# power.net
KiCad netlist of a schematic drawn in EAGLE
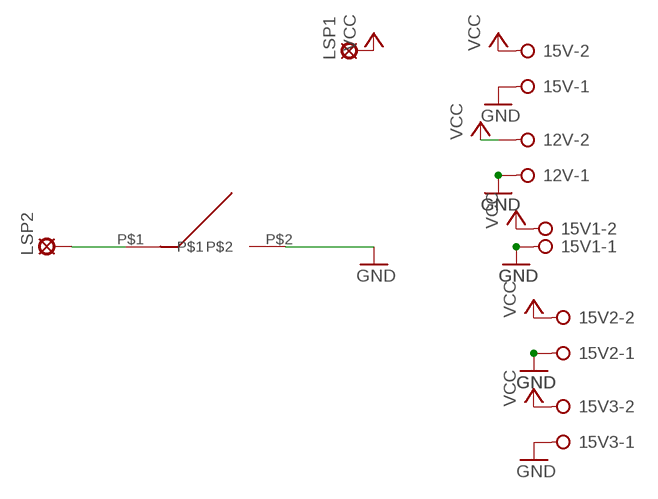
[diagram p0: schematic, sheet 1]

(export (version "E")
  (design (tool "Eeschema 10.0.6"))
  (components
    (comp (ref "12V")
      (value "W237-02P")
      (footprint "eagle-import:W237-132")
      (libsource (lib "eagle-import") (part "W237-02P"))
    )
    (comp (ref "15V")
      (value "W237-02P")
      (footprint "eagle-import:W237-132")
      (libsource (lib "eagle-import") (part "W237-02P"))
    )
    (comp (ref "15V1")
      (value "W237-02P")
      (footprint "eagle-import:W237-132")
      (libsource (lib "eagle-import") (part "W237-02P"))
    )
    (comp (ref "15V2")
      (value "W237-02P")
      (footprint "eagle-import:W237-132")
      (libsource (lib "eagle-import") (part "W237-02P"))
    )
    (comp (ref "15V3")
      (value "W237-02P")
      (footprint "eagle-import:W237-132")
      (libsource (lib "eagle-import") (part "W237-02P"))
    )
    (comp (ref "LSP1")
      (value "SE14")
      (footprint "eagle-import:SE14")
      (libsource (lib "eagle-import") (part "SE14"))
    )
    (comp (ref "LSP2")
      (value "SE14")
      (footprint "eagle-import:SE14")
      (libsource (lib "eagle-import") (part "SE14"))
    )
    (comp (ref "U$1")
      (value "ON/OFF")
      (footprint "eagle-import:ON_OFF")
      (libsource (lib "eagle-import") (part "ON/OFF"))
    )
  )
  (nets
    (net (code "1") (name "GND") (class "Default")
      (node (ref "12V") (pin "1") (pinfunction "KL_1") (pintype "passive"))
      (node (ref "15V") (pin "1") (pinfunction "KL_1") (pintype "passive"))
      (node (ref "15V1") (pin "1") (pinfunction "KL_1") (pintype "passive"))
      (node (ref "15V2") (pin "1") (pinfunction "KL_1") (pintype "passive"))
      (node (ref "15V3") (pin "1") (pinfunction "KL_1") (pintype "passive"))
      (node (ref "U$1") (pin "P$2") (pinfunction "P$2_P$2") (pintype "bidirectional"))
    )
    (net (code "2") (name "Net-(LSP2-PadMP)") (class "Default")
      (node (ref "LSP2") (pin "MP") (pinfunction "MP_MP") (pintype "passive"))
      (node (ref "U$1") (pin "P$1") (pinfunction "P$1_P$1") (pintype "bidirectional"))
    )
    (net (code "3") (name "VCC") (class "Default")
      (node (ref "12V") (pin "2") (pinfunction "KL_2") (pintype "passive"))
      (node (ref "15V") (pin "2") (pinfunction "KL_2") (pintype "passive"))
      (node (ref "15V1") (pin "2") (pinfunction "KL_2") (pintype "passive"))
      (node (ref "15V2") (pin "2") (pinfunction "KL_2") (pintype "passive"))
      (node (ref "15V3") (pin "2") (pinfunction "KL_2") (pintype "passive"))
      (node (ref "LSP1") (pin "MP") (pinfunction "MP_MP") (pintype "passive"))
    )
  )
)
